# Sheet4.net
KiCad netlist of a schematic drawn in Altium Designer
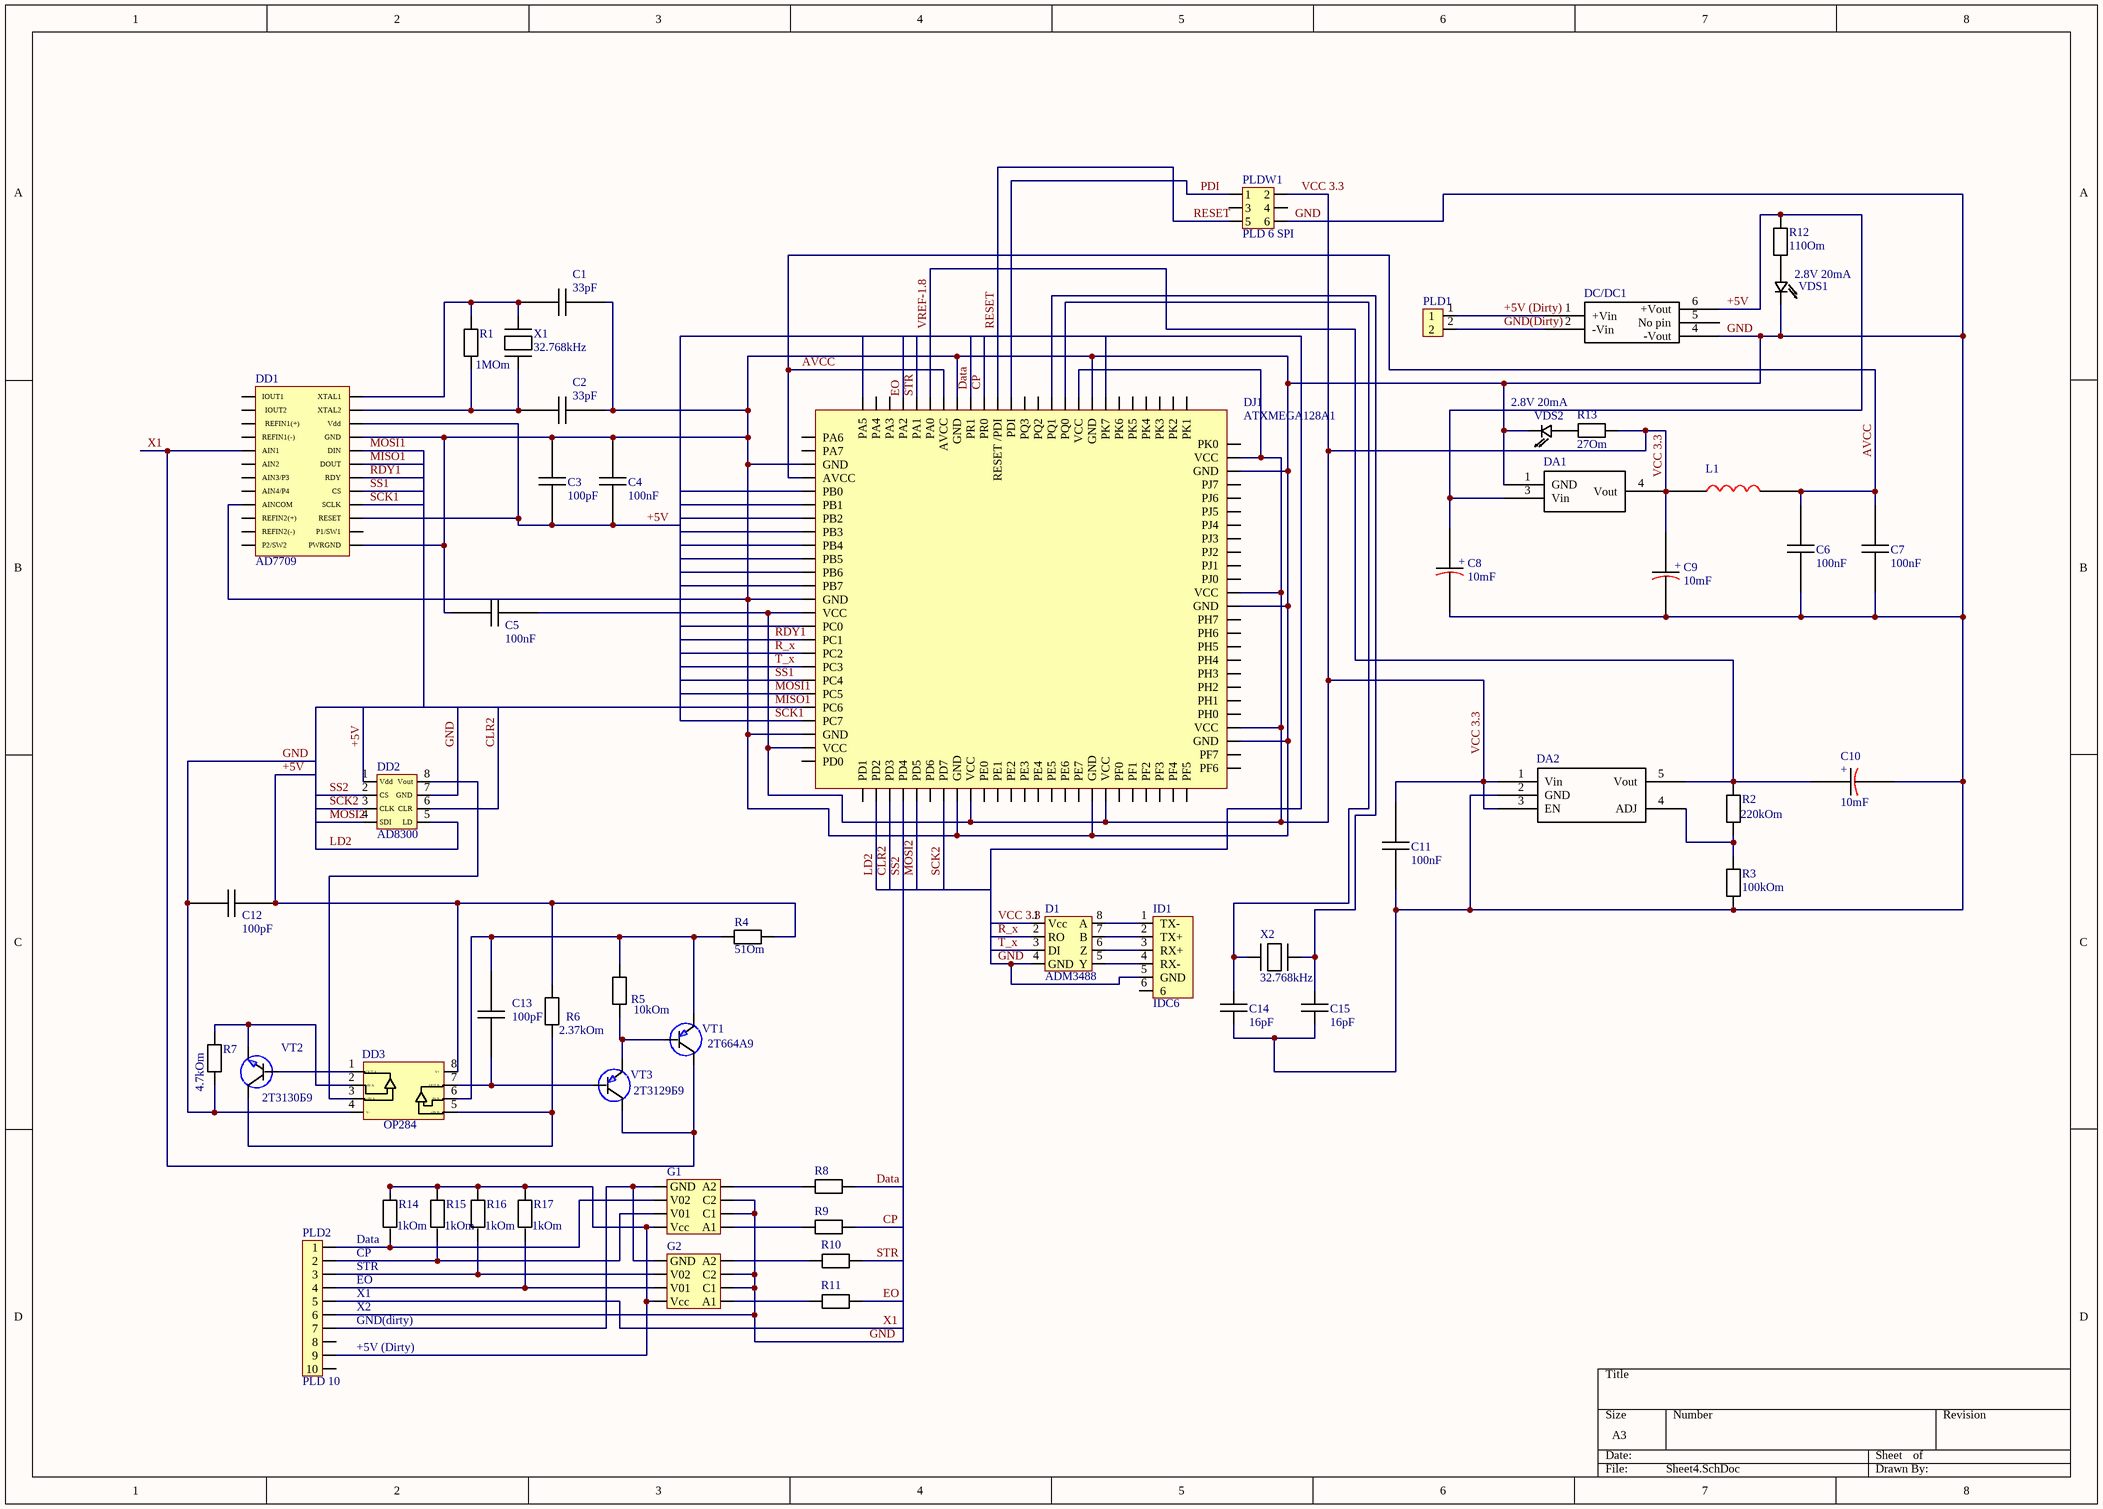
[diagram p0: Sheet4.SchDoc]

(export (version "E")
  (design (tool "Eeschema 10.0.6"))
  (components
    (comp (ref "C1") (value "33pF") (footprint "Cap 1206") (libsource (lib "Schlib1") (part "Cap 33pF")))
    (comp (ref "C2") (value "33pF") (footprint "Cap 1206") (libsource (lib "Schlib1") (part "Cap 33pF")))
    (comp (ref "C3") (value "100pF") (footprint "Cap 0805") (libsource (lib "Schlib1") (part "Cap 100 pF")))
    (comp (ref "C4") (value "100nF") (footprint "Cap 0805") (libsource (lib "Schlib1") (part "cap 100nF")))
    (comp (ref "C5") (value "100nF") (footprint "Cap 0805") (libsource (lib "Schlib1") (part "cap 100nF")))
    (comp (ref "C6") (value "100nF") (footprint "Cap 0805") (libsource (lib "Schlib1") (part "cap 100nF")))
    (comp (ref "C7") (value "100nF") (footprint "Cap 0805") (libsource (lib "Schlib1") (part "cap 100nF")))
    (comp (ref "C8")
      (value "10mF")
      (footprint "Cap 10mF electrolit")
      (libsource (lib "Schlib1") (part "Cap 10mF electrolit"))
    )
    (comp (ref "C9")
      (value "10mF")
      (footprint "Cap 10mF electrolit")
      (libsource (lib "Schlib1") (part "Cap 10mF electrolit"))
    )
    (comp (ref "C10")
      (value "10mF")
      (footprint "Cap 10mF electrolit")
      (libsource (lib "Schlib1") (part "Cap 10mF electrolit"))
    )
    (comp (ref "C11") (value "100nF") (footprint "Cap 0805") (libsource (lib "Schlib1") (part "cap 100nF")))
    (comp (ref "C12") (value "100pF") (footprint "Cap 0805") (libsource (lib "Schlib1") (part "Cap 100pF")))
    (comp (ref "C13") (value "100pF") (footprint "Cap 0805") (libsource (lib "Schlib1") (part "Cap 100pF")))
    (comp (ref "C14") (value "16pF") (footprint "Cap 0805") (libsource (lib "Schlib1") (part "Cap 22pF")))
    (comp (ref "C15") (value "16pF") (footprint "Cap 0805") (libsource (lib "Schlib1") (part "Cap 22pF")))
    (comp (ref "D1") (value "ADM3488") (footprint "ADM3488") (libsource (lib "Schlib1") (part "ADM3488")))
    (comp (ref "DA1") (value "~") (footprint "MC33269") (libsource (lib "Schlib1") (part "MC33269")))
    (comp (ref "DA2") (value "~") (footprint "MIC5205-ADJ") (libsource (lib "Schlib1") (part "MIC5205-ADJ")))
    (comp (ref "DC/DC1")
      (value "~")
      (footprint "TRACO POWER")
      (libsource (lib "Schlib1") (part "TRACO POWER(5V)"))
    )
    (comp (ref "DD1")
      (value "AD7709")
      (footprint "AD7709 TSSOP24")
      (libsource (lib "Schlib1") (part "AD7709"))
    )
    (comp (ref "DD2") (value "AD8300") (footprint "SOIC8") (libsource (lib "Schlib1") (part "AD8300")))
    (comp (ref "DD3") (value "OP284") (footprint "SOIC8") (libsource (lib "Schlib1") (part "OP284")))
    (comp (ref "DJ1")
      (value "ATXMEGA128A1")
      (footprint "ATXMEGA128A1")
      (libsource (lib "Schlib1") (part "ATXMEGA128A1"))
    )
    (comp (ref "G1")
      (value "~")
      (footprint "HCPL-0600/01/11/30/31/61 (HCPL-0631-000E)")
      (libsource (lib "altium-import") (part "root_2__Schlib1.SchLib"))
    )
    (comp (ref "G2")
      (value "~")
      (footprint "HCPL-0600/01/11/30/31/61 (HCPL-0631-000E)")
      (libsource (lib "altium-import") (part "root_2__Schlib1.SchLib"))
    )
    (comp (ref "ID1") (value "IDC6") (footprint "IDC 6") (libsource (lib "Schlib1") (part "IDC6")))
    (comp (ref "L1") (value "~") (footprint "Ind 10 mHe") (libsource (lib "Schlib1") (part "Ind 10 mHe")))
    (comp (ref "PLD1") (value "~") (footprint "PLS 2") (libsource (lib "Schlib1") (part "PLS 2")))
    (comp (ref "PLD2") (value "PLD 10") (footprint "PLD 10") (libsource (lib "Schlib1") (part "PLD 10")))
    (comp (ref "PLDW1")
      (value "PLD 6 SPI")
      (footprint "PLD 6 SPI")
      (libsource (lib "Schlib1") (part "PLD 6 SPI"))
    )
    (comp (ref "R1") (value "1MOm") (footprint "Res 1206") (libsource (lib "Schlib1") (part "RES 1MOm")))
    (comp (ref "R2") (value "220kOm") (footprint "Res 0805") (libsource (lib "Schlib1") (part "Res 100kOm")))
    (comp (ref "R3") (value "100kOm") (footprint "Res 0805") (libsource (lib "Schlib1") (part "Res 100kOm")))
    (comp (ref "R4") (value "51Om") (footprint "Res 1206") (libsource (lib "Schlib1") (part "RES 51Om")))
    (comp (ref "R5")
      (value "10kOm")
      (footprint "Res 1206")
      (libsource (lib "Schlib1") (part "RES 10kOm SMD1206"))
    )
    (comp (ref "R6")
      (value "2.37kOm")
      (footprint "Res 1206")
      (libsource (lib "Schlib1") (part "RES 2.37kOm"))
    )
    (comp (ref "R7") (value "4.7kOm") (footprint "Res 0805") (libsource (lib "Schlib1") (part "RES 4.6kOm")))
    (comp (ref "R8") (value "~") (footprint "Res 0805") (libsource (lib "Schlib1") (part "Res 100 Om")))
    (comp (ref "R9") (value "~") (footprint "Res 0805") (libsource (lib "Schlib1") (part "Res 100 Om")))
    (comp (ref "R10") (value "~") (footprint "Res 0805") (libsource (lib "Schlib1") (part "Res 100 Om")))
    (comp (ref "R11") (value "~") (footprint "Res 0805") (libsource (lib "Schlib1") (part "Res 100 Om")))
    (comp (ref "R12") (value "110Om") (footprint "Res 0805") (libsource (lib "Schlib1") (part "Res 110Om")))
    (comp (ref "R13") (value "27Om") (footprint "Res 0805") (libsource (lib "Schlib1") (part "Res 25Om")))
    (comp (ref "R14") (value "1kOm") (footprint "Cap 0603") (libsource (lib "Schlib1") (part "Res 1kOm")))
    (comp (ref "R15") (value "1kOm") (footprint "Cap 0603") (libsource (lib "Schlib1") (part "Res 1kOm")))
    (comp (ref "R16") (value "1kOm") (footprint "Cap 0603") (libsource (lib "Schlib1") (part "Res 1kOm")))
    (comp (ref "R17") (value "1kOm") (footprint "Cap 0603") (libsource (lib "Schlib1") (part "Res 1kOm")))
    (comp (ref "VDS1")
      (value "2.8V 20mA")
      (footprint "Под диод (5ммх2мм)")
      (libsource (lib "Schlib1") (part "Светодиод"))
    )
    (comp (ref "VDS2")
      (value "2.8V 20mA")
      (footprint "Под диод (5ммх2мм)")
      (libsource (lib "Schlib1") (part "Светодиод"))
    )
    (comp (ref "VT1") (value "2Т664А9") (footprint "2Т3129Б9") (libsource (lib "Schlib1") (part "2Т664А9")))
    (comp (ref "VT2") (value "2Т3130Б9") (footprint "2Т3129Б9") (libsource (lib "Schlib1") (part "2Т3130Б9")))
    (comp (ref "VT3") (value "2Т3129Б9") (footprint "2Т3129Б9") (libsource (lib "Schlib1") (part "2Т3129Б9")))
    (comp (ref "X1") (value "32.768kHz") (footprint "kvarz") (libsource (lib "Schlib1") (part "32.768kHz")))
    (comp (ref "X2") (value "32.768kHz") (footprint "kvarz") (libsource (lib "Schlib1") (part "32.768kHz")))
  )
  (nets
    (net (code "1") (name "/+5V") (class "Default")
      (node (ref "C12") (pin "2") (pinfunction "2_2") (pintype "passive"))
      (node (ref "C3") (pin "1") (pinfunction "1_1") (pintype "passive"))
      (node (ref "C4") (pin "1") (pinfunction "1_1") (pintype "passive"))
      (node (ref "C8") (pin "1") (pinfunction "1_1") (pintype "passive"))
      (node (ref "DA1") (pin "3") (pinfunction "Vin_3") (pintype "passive"))
      (node (ref "DC/DC1") (pin "6") (pinfunction "+Vout_6") (pintype "passive"))
      (node (ref "DD1") (pin "15") (pinfunction "RESET_15") (pintype "passive"))
      (node (ref "DD1") (pin "22") (pinfunction "Vdd_22") (pintype "passive"))
      (node (ref "DD2") (pin "1") (pinfunction "Vdd_1") (pintype "passive"))
      (node (ref "DD3") (pin "8") (pinfunction "V+_8") (pintype "passive"))
      (node (ref "R12") (pin "2") (pinfunction "2_2") (pintype "passive"))
      (node (ref "R4") (pin "2") (pinfunction "2_2") (pintype "passive"))
      (node (ref "R6") (pin "2") (pinfunction "2_2") (pintype "passive"))
    )
    (net (code "2") (name "/+5V (Dirty)") (class "Default")
      (node (ref "DC/DC1") (pin "1") (pinfunction "+Vin_1") (pintype "passive"))
      (node (ref "PLD1") (pin "1") (pinfunction "1_1") (pintype "passive"))
    )
    (net (code "3") (name "/AVCC") (class "Default")
      (node (ref "C6") (pin "2") (pinfunction "2_2") (pintype "passive"))
      (node (ref "C7") (pin "2") (pinfunction "2_2") (pintype "passive"))
      (node (ref "DJ1") (pin "H1") (pinfunction "AVCC_H1") (pintype "passive"))
      (node (ref "DJ1") (pin "K4") (pinfunction "AVCC_K4") (pintype "passive"))
      (node (ref "L1") (pin "2") (pinfunction "2_2") (pintype "passive"))
    )
    (net (code "4") (name "/CLR2") (class "Default")
      (node (ref "DD2") (pin "6") (pinfunction "CLR_6") (pintype "passive"))
      (node (ref "DJ1") (pin "H10") (pinfunction "PD3_H10") (pintype "passive"))
    )
    (net (code "5") (name "/CP") (class "Default")
      (node (ref "DJ1") (pin "F2") (pinfunction "PR0_F2") (pintype "passive"))
      (node (ref "R9") (pin "2") (pinfunction "2_2") (pintype "passive"))
    )
    (net (code "6") (name "/Data") (class "Default")
      (node (ref "DJ1") (pin "F1") (pinfunction "PR1_F1") (pintype "passive"))
      (node (ref "R8") (pin "2") (pinfunction "2_2") (pintype "passive"))
    )
    (net (code "7") (name "/EO") (class "Default")
      (node (ref "DJ1") (pin "H2") (pinfunction "PA2_H2") (pintype "passive"))
      (node (ref "R11") (pin "2") (pinfunction "2_2") (pintype "passive"))
    )
    (net (code "8") (name "/GND") (class "Default")
      (node (ref "C1") (pin "2") (pinfunction "2_2") (pintype "passive"))
      (node (ref "C10") (pin "2") (pinfunction "2_2") (pintype "passive"))
      (node (ref "C11") (pin "1") (pinfunction "1_1") (pintype "passive"))
      (node (ref "C12") (pin "1") (pinfunction "1_1") (pintype "passive"))
      (node (ref "C14") (pin "1") (pinfunction "1_1") (pintype "passive"))
      (node (ref "C15") (pin "1") (pinfunction "1_1") (pintype "passive"))
      (node (ref "C2") (pin "2") (pinfunction "2_2") (pintype "passive"))
      (node (ref "C3") (pin "2") (pinfunction "2_2") (pintype "passive"))
      (node (ref "C4") (pin "2") (pinfunction "2_2") (pintype "passive"))
      (node (ref "C5") (pin "1") (pinfunction "1_1") (pintype "passive"))
      (node (ref "C6") (pin "1") (pinfunction "1_1") (pintype "passive"))
      (node (ref "C7") (pin "1") (pinfunction "1_1") (pintype "passive"))
      (node (ref "C8") (pin "2") (pinfunction "2_2") (pintype "passive"))
      (node (ref "C9") (pin "2") (pinfunction "2_2") (pintype "passive"))
      (node (ref "D1") (pin "4") (pinfunction "GND_4") (pintype "passive"))
      (node (ref "DA1") (pin "1") (pinfunction "GND_1") (pintype "passive"))
      (node (ref "DA2") (pin "2") (pinfunction "GND_2") (pintype "passive"))
      (node (ref "DC/DC1") (pin "4") (pinfunction "-Vout_4") (pintype "passive"))
      (node (ref "DD1") (pin "13") (pinfunction "PWRGND_13") (pintype "passive"))
      (node (ref "DD1") (pin "21") (pinfunction "GND_21") (pintype "passive"))
      (node (ref "DD1") (pin "9") (pinfunction "AINCOM_9") (pintype "passive"))
      (node (ref "DD2") (pin "7") (pinfunction "GND_7") (pintype "passive"))
      (node (ref "DD3") (pin "4") (pinfunction "V-_4") (pintype "passive"))
      (node (ref "DJ1") (pin "A3") (pinfunction "GND_A3") (pintype "passive"))
      (node (ref "DJ1") (pin "A6") (pinfunction "GND_A6") (pintype "passive"))
      (node (ref "DJ1") (pin "A8") (pinfunction "GND_A8") (pintype "passive"))
      (node (ref "DJ1") (pin "D1") (pinfunction "GND_D1") (pintype "passive"))
      (node (ref "DJ1") (pin "D10") (pinfunction "GND_D10") (pintype "passive"))
      (node (ref "DJ1") (pin "G1") (pinfunction "GND_G1") (pintype "passive"))
      (node (ref "DJ1") (pin "G10") (pinfunction "GND_G10") (pintype "passive"))
      (node (ref "DJ1") (pin "K3") (pinfunction "GND_K3") (pintype "passive"))
      (node (ref "DJ1") (pin "K7") (pinfunction "GND_K7") (pintype "passive"))
      (node (ref "DJ1") (pin "K9") (pinfunction "GND_K9") (pintype "passive"))
      (node (ref "G1") (pin "2") (pinfunction "C1_2") (pintype "passive"))
      (node (ref "G1") (pin "3") (pinfunction "C2_3") (pintype "passive"))
      (node (ref "G2") (pin "2") (pinfunction "C1_2") (pintype "passive"))
      (node (ref "G2") (pin "3") (pinfunction "C2_3") (pintype "passive"))
      (node (ref "ID1") (pin "5") (pinfunction "GND_5") (pintype "passive"))
      (node (ref "PLD2") (pin "6") (pinfunction "6_6") (pintype "passive"))
      (node (ref "PLDW1") (pin "6") (pinfunction "6_6") (pintype "passive"))
      (node (ref "R3") (pin "1") (pinfunction "1_1") (pintype "passive"))
      (node (ref "R7") (pin "1") (pinfunction "1_1") (pintype "passive"))
      (node (ref "VDS1") (pin "2") (pinfunction "2_2") (pintype "passive"))
      (node (ref "VDS2") (pin "2") (pinfunction "2_2") (pintype "passive"))
    )
    (net (code "9") (name "/GND(Dirty)") (class "Default")
      (node (ref "DC/DC1") (pin "2") (pinfunction "-Vin_2") (pintype "passive"))
      (node (ref "PLD1") (pin "2") (pinfunction "2_2") (pintype "passive"))
    )
    (net (code "10") (name "/LD2") (class "Default")
      (node (ref "DD2") (pin "5") (pinfunction "LD_5") (pintype "passive"))
      (node (ref "DJ1") (pin "J9") (pinfunction "PD2_J9") (pintype "passive"))
    )
    (net (code "11") (name "/MISO1") (class "Default")
      (node (ref "DD1") (pin "19") (pinfunction "DOUT_19") (pintype "passive"))
      (node (ref "DJ1") (pin "G7") (pinfunction "PC6_G7") (pintype "passive"))
    )
    (net (code "12") (name "/MOSI1") (class "Default")
      (node (ref "DD1") (pin "20") (pinfunction "DIN_20") (pintype "passive"))
      (node (ref "DJ1") (pin "H7") (pinfunction "PC5_H7") (pintype "passive"))
    )
    (net (code "13") (name "/MOSI2") (class "Default")
      (node (ref "DD2") (pin "4") (pinfunction "SDI_4") (pintype "passive"))
      (node (ref "DJ1") (pin "H8") (pinfunction "PD5_H8") (pintype "passive"))
    )
    (net (code "14") (name "/PDI") (class "Default")
      (node (ref "DJ1") (pin "F4") (pinfunction "PDI_F4") (pintype "passive"))
      (node (ref "PLDW1") (pin "1") (pinfunction "1_1") (pintype "passive"))
    )
    (net (code "15") (name "/RDY1") (class "Default")
      (node (ref "DD1") (pin "18") (pinfunction "RDY_18") (pintype "passive"))
      (node (ref "DJ1") (pin "G6") (pinfunction "PC1_G6") (pintype "passive"))
    )
    (net (code "16") (name "/RESET") (class "Default")
      (node (ref "DJ1") (pin "F3") (pinfunction "RESET_/PDI_F3") (pintype "passive"))
      (node (ref "PLDW1") (pin "5") (pinfunction "5_5") (pintype "passive"))
    )
    (net (code "17") (name "/R_x") (class "Default")
      (node (ref "D1") (pin "2") (pinfunction "RO_2") (pintype "passive"))
      (node (ref "DJ1") (pin "F6") (pinfunction "PC2_F6") (pintype "passive"))
    )
    (net (code "18") (name "/SCK1") (class "Default")
      (node (ref "DD1") (pin "16") (pinfunction "SCLK_16") (pintype "passive"))
      (node (ref "DJ1") (pin "J8") (pinfunction "PC7_J8") (pintype "passive"))
    )
    (net (code "19") (name "/SCK2") (class "Default")
      (node (ref "DD2") (pin "3") (pinfunction "CLK_3") (pintype "passive"))
      (node (ref "DJ1") (pin "G8") (pinfunction "PD7_G8") (pintype "passive"))
    )
    (net (code "20") (name "/SS1") (class "Default")
      (node (ref "DD1") (pin "17") (pinfunction "CS_17") (pintype "passive"))
      (node (ref "DJ1") (pin "J7") (pinfunction "PC4_J7") (pintype "passive"))
    )
    (net (code "21") (name "/SS2") (class "Default")
      (node (ref "DD2") (pin "2") (pinfunction "CS_2") (pintype "passive"))
      (node (ref "DJ1") (pin "H9") (pinfunction "PD4_H9") (pintype "passive"))
    )
    (net (code "22") (name "/STR") (class "Default")
      (node (ref "DJ1") (pin "G2") (pinfunction "PA1_G2") (pintype "passive"))
      (node (ref "R10") (pin "2") (pinfunction "2_2") (pintype "passive"))
    )
    (net (code "23") (name "/T_x") (class "Default")
      (node (ref "D1") (pin "3") (pinfunction "DI_3") (pintype "passive"))
      (node (ref "DJ1") (pin "J6") (pinfunction "PC3_J6") (pintype "passive"))
    )
    (net (code "24") (name "/VCC 3.3") (class "Default")
      (node (ref "C11") (pin "2") (pinfunction "2_2") (pintype "passive"))
      (node (ref "C5") (pin "2") (pinfunction "2_2") (pintype "passive"))
      (node (ref "C9") (pin "1") (pinfunction "1_1") (pintype "passive"))
      (node (ref "D1") (pin "1") (pinfunction "Vcc_1") (pintype "passive"))
      (node (ref "DA1") (pin "4") (pinfunction "Vout_4") (pintype "passive"))
      (node (ref "DA2") (pin "1") (pinfunction "Vin_1") (pintype "passive"))
      (node (ref "DA2") (pin "3") (pinfunction "EN_3") (pintype "passive"))
      (node (ref "DJ1") (pin "A2") (pinfunction "VCC_A2") (pintype "passive"))
      (node (ref "DJ1") (pin "A5") (pinfunction "VCC_A5") (pintype "passive"))
      (node (ref "DJ1") (pin "A9") (pinfunction "VCC_A9") (pintype "passive"))
      (node (ref "DJ1") (pin "C1") (pinfunction "VCC_C1") (pintype "passive"))
      (node (ref "DJ1") (pin "C10") (pinfunction "VCC_C10") (pintype "passive"))
      (node (ref "DJ1") (pin "F10") (pinfunction "VCC_F10") (pintype "passive"))
      (node (ref "DJ1") (pin "K6") (pinfunction "VCC_K6") (pintype "passive"))
      (node (ref "DJ1") (pin "K8") (pinfunction "VCC_K8") (pintype "passive"))
      (node (ref "L1") (pin "1") (pinfunction "1_1") (pintype "passive"))
      (node (ref "PLDW1") (pin "2") (pinfunction "2_2") (pintype "passive"))
      (node (ref "R13") (pin "1") (pinfunction "1_1") (pintype "passive"))
    )
    (net (code "25") (name "/VREF-1.8") (class "Default")
      (node (ref "C10") (pin "1") (pinfunction "1_1") (pintype "passive"))
      (node (ref "DA2") (pin "5") (pinfunction "Vout_5") (pintype "passive"))
      (node (ref "DJ1") (pin "J1") (pinfunction "PA0_J1") (pintype "passive"))
      (node (ref "R2") (pin "2") (pinfunction "2_2") (pintype "passive"))
    )
    (net (code "26") (name "/X1") (class "Default")
      (node (ref "DD1") (pin "5") (pinfunction "AIN1_5") (pintype "passive"))
      (node (ref "PLD2") (pin "5") (pinfunction "5_5") (pintype "passive"))
      (node (ref "VT1") (pin "1") (pinfunction "1_1") (pintype "passive"))
      (node (ref "VT3") (pin "2") (pinfunction "2_2") (pintype "passive"))
    )
    (net (code "27") (name "Net-(D1-A)") (class "Default")
      (node (ref "D1") (pin "8") (pinfunction "A_8") (pintype "passive"))
      (node (ref "ID1") (pin "1") (pinfunction "TX-_1") (pintype "passive"))
    )
    (net (code "28") (name "Net-(D1-B)") (class "Default")
      (node (ref "D1") (pin "7") (pinfunction "B_7") (pintype "passive"))
      (node (ref "ID1") (pin "2") (pinfunction "TX+_2") (pintype "passive"))
    )
    (net (code "29") (name "Net-(D1-Y)") (class "Default")
      (node (ref "D1") (pin "5") (pinfunction "Y_5") (pintype "passive"))
      (node (ref "ID1") (pin "4") (pinfunction "RX-_4") (pintype "passive"))
    )
    (net (code "30") (name "Net-(D1-Z)") (class "Default")
      (node (ref "D1") (pin "6") (pinfunction "Z_6") (pintype "passive"))
      (node (ref "ID1") (pin "3") (pinfunction "RX+_3") (pintype "passive"))
    )
    (net (code "31") (name "Net-(DA2-ADJ)") (class "Default")
      (node (ref "DA2") (pin "4") (pinfunction "ADJ_4") (pintype "passive"))
      (node (ref "R2") (pin "1") (pinfunction "1_1") (pintype "passive"))
      (node (ref "R3") (pin "2") (pinfunction "2_2") (pintype "passive"))
    )
    (net (code "32") (name "Net-(DD1-XTAL1)") (class "Default")
      (node (ref "C1") (pin "1") (pinfunction "1_1") (pintype "passive"))
      (node (ref "DD1") (pin "24") (pinfunction "XTAL1_24") (pintype "passive"))
      (node (ref "R1") (pin "2") (pinfunction "2_2") (pintype "passive"))
      (node (ref "X1") (pin "2") (pinfunction "2_2") (pintype "passive"))
    )
    (net (code "33") (name "Net-(DD1-XTAL2)") (class "Default")
      (node (ref "C2") (pin "1") (pinfunction "1_1") (pintype "passive"))
      (node (ref "DD1") (pin "23") (pinfunction "XTAL2_23") (pintype "passive"))
      (node (ref "R1") (pin "1") (pinfunction "1_1") (pintype "passive"))
      (node (ref "X1") (pin "1") (pinfunction "1_1") (pintype "passive"))
    )
    (net (code "34") (name "Net-(DD2-Vout)") (class "Default")
      (node (ref "DD2") (pin "8") (pinfunction "Vout_8") (pintype "passive"))
      (node (ref "DD3") (pin "3") (pinfunction "+IN_A_3") (pintype "passive"))
    )
    (net (code "35") (name "Net-(DD3-+IN_B)") (class "Default")
      (node (ref "DD3") (pin "5") (pinfunction "+IN_B_5") (pintype "passive"))
      (node (ref "R6") (pin "1") (pinfunction "1_1") (pintype "passive"))
      (node (ref "VT2") (pin "2") (pinfunction "2_2") (pintype "passive"))
    )
    (net (code "36") (name "Net-(DD3--IN_A)") (class "Default")
      (node (ref "DD3") (pin "2") (pinfunction "-IN_A_2") (pintype "passive"))
      (node (ref "R7") (pin "2") (pinfunction "2_2") (pintype "passive"))
      (node (ref "VT2") (pin "3") (pinfunction "3_3") (pintype "passive"))
    )
    (net (code "37") (name "Net-(DD3--IN_B)") (class "Default")
      (node (ref "C13") (pin "1") (pinfunction "1_1") (pintype "passive"))
      (node (ref "DD3") (pin "6") (pinfunction "-IN_B_6") (pintype "passive"))
      (node (ref "R4") (pin "1") (pinfunction "1_1") (pintype "passive"))
      (node (ref "R5") (pin "2") (pinfunction "2_2") (pintype "passive"))
      (node (ref "VT1") (pin "3") (pinfunction "3_3") (pintype "passive"))
    )
    (net (code "38") (name "Net-(DD3-OUT_A)") (class "Default")
      (node (ref "DD3") (pin "1") (pinfunction "OUT_A_1") (pintype "passive"))
      (node (ref "VT2") (pin "1") (pinfunction "1_1") (pintype "passive"))
    )
    (net (code "39") (name "Net-(DD3-OUT_B)") (class "Default")
      (node (ref "C13") (pin "2") (pinfunction "2_2") (pintype "passive"))
      (node (ref "DD3") (pin "7") (pinfunction "OUT_B_7") (pintype "passive"))
      (node (ref "VT3") (pin "1") (pinfunction "1_1") (pintype "passive"))
    )
    (net (code "40") (name "Net-(DJ1-PQ0)") (class "Default")
      (node (ref "C14") (pin "2") (pinfunction "2_2") (pintype "passive"))
      (node (ref "DJ1") (pin "E1") (pinfunction "PQ0_E1") (pintype "passive"))
      (node (ref "X2") (pin "1") (pinfunction "1_1") (pintype "passive"))
    )
    (net (code "41") (name "Net-(DJ1-PQ1)") (class "Default")
      (node (ref "C15") (pin "2") (pinfunction "2_2") (pintype "passive"))
      (node (ref "DJ1") (pin "E2") (pinfunction "PQ1_E2") (pintype "passive"))
      (node (ref "X2") (pin "2") (pinfunction "2_2") (pintype "passive"))
    )
    (net (code "42") (name "Net-(G1-A1)") (class "Default")
      (node (ref "G1") (pin "1") (pinfunction "A1_1") (pintype "passive"))
      (node (ref "R9") (pin "1") (pinfunction "1_1") (pintype "passive"))
    )
    (net (code "43") (name "Net-(G1-A2)") (class "Default")
      (node (ref "G1") (pin "4") (pinfunction "A2_4") (pintype "passive"))
      (node (ref "R8") (pin "1") (pinfunction "1_1") (pintype "passive"))
    )
    (net (code "44") (name "Net-(G1-GND)") (class "Default")
      (node (ref "G1") (pin "5") (pinfunction "GND_5") (pintype "passive"))
      (node (ref "G2") (pin "5") (pinfunction "GND_5") (pintype "passive"))
      (node (ref "PLD2") (pin "7") (pinfunction "7_7") (pintype "passive"))
    )
    (net (code "45") (name "Net-(G1-V01)") (class "Default")
      (node (ref "G1") (pin "7") (pinfunction "V01_7") (pintype "passive"))
      (node (ref "PLD2") (pin "2") (pinfunction "2_2") (pintype "passive"))
      (node (ref "R15") (pin "1") (pinfunction "1_1") (pintype "passive"))
    )
    (net (code "46") (name "Net-(G1-V02)") (class "Default")
      (node (ref "G1") (pin "6") (pinfunction "V02_6") (pintype "passive"))
      (node (ref "PLD2") (pin "1") (pinfunction "1_1") (pintype "passive"))
      (node (ref "R14") (pin "1") (pinfunction "1_1") (pintype "passive"))
    )
    (net (code "47") (name "Net-(G1-Vcc)") (class "Default")
      (node (ref "G1") (pin "8") (pinfunction "Vcc_8") (pintype "passive"))
      (node (ref "G2") (pin "8") (pinfunction "Vcc_8") (pintype "passive"))
      (node (ref "PLD2") (pin "9") (pinfunction "9_9") (pintype "passive"))
      (node (ref "R14") (pin "2") (pinfunction "2_2") (pintype "passive"))
      (node (ref "R15") (pin "2") (pinfunction "2_2") (pintype "passive"))
      (node (ref "R16") (pin "2") (pinfunction "2_2") (pintype "passive"))
      (node (ref "R17") (pin "2") (pinfunction "2_2") (pintype "passive"))
    )
    (net (code "48") (name "Net-(G2-A1)") (class "Default")
      (node (ref "G2") (pin "1") (pinfunction "A1_1") (pintype "passive"))
      (node (ref "R11") (pin "1") (pinfunction "1_1") (pintype "passive"))
    )
    (net (code "49") (name "Net-(G2-A2)") (class "Default")
      (node (ref "G2") (pin "4") (pinfunction "A2_4") (pintype "passive"))
      (node (ref "R10") (pin "1") (pinfunction "1_1") (pintype "passive"))
    )
    (net (code "50") (name "Net-(G2-V01)") (class "Default")
      (node (ref "G2") (pin "7") (pinfunction "V01_7") (pintype "passive"))
      (node (ref "PLD2") (pin "4") (pinfunction "4_4") (pintype "passive"))
      (node (ref "R17") (pin "1") (pinfunction "1_1") (pintype "passive"))
    )
    (net (code "51") (name "Net-(G2-V02)") (class "Default")
      (node (ref "G2") (pin "6") (pinfunction "V02_6") (pintype "passive"))
      (node (ref "PLD2") (pin "3") (pinfunction "3_3") (pintype "passive"))
      (node (ref "R16") (pin "1") (pinfunction "1_1") (pintype "passive"))
    )
    (net (code "52") (name "Net-(R5-Pad1)") (class "Default")
      (node (ref "R5") (pin "1") (pinfunction "1_1") (pintype "passive"))
      (node (ref "VT1") (pin "2") (pinfunction "2_2") (pintype "passive"))
      (node (ref "VT3") (pin "3") (pinfunction "3_3") (pintype "passive"))
    )
    (net (code "53") (name "Net-(R12-Pad1)") (class "Default")
      (node (ref "R12") (pin "1") (pinfunction "1_1") (pintype "passive"))
      (node (ref "VDS1") (pin "1") (pinfunction "1_1") (pintype "passive"))
    )
    (net (code "54") (name "Net-(R13-Pad2)") (class "Default")
      (node (ref "R13") (pin "2") (pinfunction "2_2") (pintype "passive"))
      (node (ref "VDS2") (pin "1") (pinfunction "1_1") (pintype "passive"))
    )
    (net (code "55") (name "unconnected-(DC/DC1-No_pin-Pad5)") (class "Default")
      (node (ref "DC/DC1") (pin "5") (pinfunction "No_pin_5") (pintype "passive"))
    )
    (net (code "56") (name "unconnected-(DD1-AIN2-Pad6)") (class "Default")
      (node (ref "DD1") (pin "6") (pinfunction "AIN2_6") (pintype "passive"))
    )
    (net (code "57") (name "unconnected-(DD1-AIN3{slash}P3-Pad7)") (class "Default")
      (node (ref "DD1") (pin "7") (pinfunction "AIN3/P3_7") (pintype "passive"))
    )
    (net (code "58") (name "unconnected-(DD1-AIN4{slash}P4-Pad8)") (class "Default")
      (node (ref "DD1") (pin "8") (pinfunction "AIN4/P4_8") (pintype "passive"))
    )
    (net (code "59") (name "unconnected-(DD1-IOUT1-Pad1)") (class "Default")
      (node (ref "DD1") (pin "1") (pinfunction "IOUT1_1") (pintype "passive"))
    )
    (net (code "60") (name "unconnected-(DD1-IOUT2-Pad2)") (class "Default")
      (node (ref "DD1") (pin "2") (pinfunction "IOUT2_2") (pintype "passive"))
    )
    (net (code "61") (name "unconnected-(DD1-P1{slash}SW1-Pad14)") (class "Default")
      (node (ref "DD1") (pin "14") (pinfunction "P1/SW1_14") (pintype "passive"))
    )
    (net (code "62") (name "unconnected-(DD1-P2{slash}SW2-Pad12)") (class "Default")
      (node (ref "DD1") (pin "12") (pinfunction "P2/SW2_12") (pintype "passive"))
    )
    (net (code "63") (name "unconnected-(DD1-REFIN1(+)-Pad3)") (class "Default")
      (node (ref "DD1") (pin "3") (pinfunction "REFIN1(+)_3") (pintype "passive"))
    )
    (net (code "64") (name "unconnected-(DD1-REFIN1(-)-Pad4)") (class "Default")
      (node (ref "DD1") (pin "4") (pinfunction "REFIN1(-)_4") (pintype "passive"))
    )
    (net (code "65") (name "unconnected-(DD1-REFIN2(+)-Pad10)") (class "Default")
      (node (ref "DD1") (pin "10") (pinfunction "REFIN2(+)_10") (pintype "passive"))
    )
    (net (code "66") (name "unconnected-(DD1-REFIN2(-)-Pad11)") (class "Default")
      (node (ref "DD1") (pin "11") (pinfunction "REFIN2(-)_11") (pintype "passive"))
    )
    (net (code "67") (name "unconnected-(DJ1-PA3-PadJ2)") (class "Default")
      (node (ref "DJ1") (pin "J2") (pinfunction "PA3_J2") (pintype "passive"))
    )
    (net (code "68") (name "unconnected-(DJ1-PA4-PadG3)") (class "Default")
      (node (ref "DJ1") (pin "G3") (pinfunction "PA4_G3") (pintype "passive"))
    )
    (net (code "69") (name "unconnected-(DJ1-PA5-PadH3)") (class "Default")
      (node (ref "DJ1") (pin "H3") (pinfunction "PA5_H3") (pintype "passive"))
    )
    (net (code "70") (name "unconnected-(DJ1-PA6-PadK1)") (class "Default")
      (node (ref "DJ1") (pin "K1") (pinfunction "PA6_K1") (pintype "passive"))
    )
    (net (code "71") (name "unconnected-(DJ1-PA7-PadK2)") (class "Default")
      (node (ref "DJ1") (pin "K2") (pinfunction "PA7_K2") (pintype "passive"))
    )
    (net (code "72") (name "unconnected-(DJ1-PB0-PadJ3)") (class "Default")
      (node (ref "DJ1") (pin "J3") (pinfunction "PB0_J3") (pintype "passive"))
    )
    (net (code "73") (name "unconnected-(DJ1-PB1-PadJ4)") (class "Default")
      (node (ref "DJ1") (pin "J4") (pinfunction "PB1_J4") (pintype "passive"))
    )
    (net (code "74") (name "unconnected-(DJ1-PB2-PadH4)") (class "Default")
      (node (ref "DJ1") (pin "H4") (pinfunction "PB2_H4") (pintype "passive"))
    )
    (net (code "75") (name "unconnected-(DJ1-PB3-PadG4)") (class "Default")
      (node (ref "DJ1") (pin "G4") (pinfunction "PB3_G4") (pintype "passive"))
    )
    (net (code "76") (name "unconnected-(DJ1-PB4-PadG5)") (class "Default")
      (node (ref "DJ1") (pin "G5") (pinfunction "PB4_G5") (pintype "passive"))
    )
    (net (code "77") (name "unconnected-(DJ1-PB5-PadH5)") (class "Default")
      (node (ref "DJ1") (pin "H5") (pinfunction "PB5_H5") (pintype "passive"))
    )
    (net (code "78") (name "unconnected-(DJ1-PB6-PadJ5)") (class "Default")
      (node (ref "DJ1") (pin "J5") (pinfunction "PB6_J5") (pintype "passive"))
    )
    (net (code "79") (name "unconnected-(DJ1-PB7-PadK5)") (class "Default")
      (node (ref "DJ1") (pin "K5") (pinfunction "PB7_K5") (pintype "passive"))
    )
    (net (code "80") (name "unconnected-(DJ1-PC0-PadH6)") (class "Default")
      (node (ref "DJ1") (pin "H6") (pinfunction "PC0_H6") (pintype "passive"))
    )
    (net (code "81") (name "unconnected-(DJ1-PD0-PadK10)") (class "Default")
      (node (ref "DJ1") (pin "K10") (pinfunction "PD0_K10") (pintype "passive"))
    )
    (net (code "82") (name "unconnected-(DJ1-PD1-PadJ10)") (class "Default")
      (node (ref "DJ1") (pin "J10") (pinfunction "PD1_J10") (pintype "passive"))
    )
    (net (code "83") (name "unconnected-(DJ1-PD6-PadG9)") (class "Default")
      (node (ref "DJ1") (pin "G9") (pinfunction "PD6_G9") (pintype "passive"))
    )
    (net (code "84") (name "unconnected-(DJ1-PE0-PadF9)") (class "Default")
      (node (ref "DJ1") (pin "F9") (pinfunction "PE0_F9") (pintype "passive"))
    )
    (net (code "85") (name "unconnected-(DJ1-PE1-PadF8)") (class "Default")
      (node (ref "DJ1") (pin "F8") (pinfunction "PE1_F8") (pintype "passive"))
    )
    (net (code "86") (name "unconnected-(DJ1-PE2-PadF7)") (class "Default")
      (node (ref "DJ1") (pin "F7") (pinfunction "PE2_F7") (pintype "passive"))
    )
    (net (code "87") (name "unconnected-(DJ1-PE3-PadE10)") (class "Default")
      (node (ref "DJ1") (pin "E10") (pinfunction "PE3_E10") (pintype "passive"))
    )
    (net (code "88") (name "unconnected-(DJ1-PE4-PadE9)") (class "Default")
      (node (ref "DJ1") (pin "E9") (pinfunction "PE4_E9") (pintype "passive"))
    )
    (net (code "89") (name "unconnected-(DJ1-PE5-PadE8)") (class "Default")
      (node (ref "DJ1") (pin "E8") (pinfunction "PE5_E8") (pintype "passive"))
    )
    (net (code "90") (name "unconnected-(DJ1-PE6-PadE7)") (class "Default")
      (node (ref "DJ1") (pin "E7") (pinfunction "PE6_E7") (pintype "passive"))
    )
    (net (code "91") (name "unconnected-(DJ1-PE7-PadE6)") (class "Default")
      (node (ref "DJ1") (pin "E6") (pinfunction "PE7_E6") (pintype "passive"))
    )
    (net (code "92") (name "unconnected-(DJ1-PF0-PadD7)") (class "Default")
      (node (ref "DJ1") (pin "D7") (pinfunction "PF0_D7") (pintype "passive"))
    )
    (net (code "93") (name "unconnected-(DJ1-PF1-PadD8)") (class "Default")
      (node (ref "DJ1") (pin "D8") (pinfunction "PF1_D8") (pintype "passive"))
    )
    (net (code "94") (name "unconnected-(DJ1-PF2-PadC8)") (class "Default")
      (node (ref "DJ1") (pin "C8") (pinfunction "PF2_C8") (pintype "passive"))
    )
    (net (code "95") (name "unconnected-(DJ1-PF3-PadC9)") (class "Default")
      (node (ref "DJ1") (pin "C9") (pinfunction "PF3_C9") (pintype "passive"))
    )
    (net (code "96") (name "unconnected-(DJ1-PF4-PadD9)") (class "Default")
      (node (ref "DJ1") (pin "D9") (pinfunction "PF4_D9") (pintype "passive"))
    )
    (net (code "97") (name "unconnected-(DJ1-PF5-PadB10)") (class "Default")
      (node (ref "DJ1") (pin "B10") (pinfunction "PF5_B10") (pintype "passive"))
    )
    (net (code "98") (name "unconnected-(DJ1-PF6-PadB9)") (class "Default")
      (node (ref "DJ1") (pin "B9") (pinfunction "PF6_B9") (pintype "passive"))
    )
    (net (code "99") (name "unconnected-(DJ1-PF7-PadA10)") (class "Default")
      (node (ref "DJ1") (pin "A10") (pinfunction "PF7_A10") (pintype "passive"))
    )
    (net (code "100") (name "unconnected-(DJ1-PH0-PadB8)") (class "Default")
      (node (ref "DJ1") (pin "B8") (pinfunction "PH0_B8") (pintype "passive"))
    )
    (net (code "101") (name "unconnected-(DJ1-PH1-PadA7)") (class "Default")
      (node (ref "DJ1") (pin "A7") (pinfunction "PH1_A7") (pintype "passive"))
    )
    (net (code "102") (name "unconnected-(DJ1-PH2-PadB7)") (class "Default")
      (node (ref "DJ1") (pin "B7") (pinfunction "PH2_B7") (pintype "passive"))
    )
    (net (code "103") (name "unconnected-(DJ1-PH3-PadC7)") (class "Default")
      (node (ref "DJ1") (pin "C7") (pinfunction "PH3_C7") (pintype "passive"))
    )
    (net (code "104") (name "unconnected-(DJ1-PH4-PadB6)") (class "Default")
      (node (ref "DJ1") (pin "B6") (pinfunction "PH4_B6") (pintype "passive"))
    )
    (net (code "105") (name "unconnected-(DJ1-PH5-PadC6)") (class "Default")
      (node (ref "DJ1") (pin "C6") (pinfunction "PH5_C6") (pintype "passive"))
    )
    (net (code "106") (name "unconnected-(DJ1-PH6-PadD6)") (class "Default")
      (node (ref "DJ1") (pin "D6") (pinfunction "PH6_D6") (pintype "passive"))
    )
    (net (code "107") (name "unconnected-(DJ1-PH7-PadB5)") (class "Default")
      (node (ref "DJ1") (pin "B5") (pinfunction "PH7_B5") (pintype "passive"))
    )
    (net (code "108") (name "unconnected-(DJ1-PJ0-PadC5)") (class "Default")
      (node (ref "DJ1") (pin "C5") (pinfunction "PJ0_C5") (pintype "passive"))
    )
    (net (code "109") (name "unconnected-(DJ1-PJ1-PadD5)") (class "Default")
      (node (ref "DJ1") (pin "D5") (pinfunction "PJ1_D5") (pintype "passive"))
    )
    (net (code "110") (name "unconnected-(DJ1-PJ2-PadE5)") (class "Default")
      (node (ref "DJ1") (pin "E5") (pinfunction "PJ2_E5") (pintype "passive"))
    )
    (net (code "111") (name "unconnected-(DJ1-PJ3-PadA4)") (class "Default")
      (node (ref "DJ1") (pin "A4") (pinfunction "PJ3_A4") (pintype "passive"))
    )
    (net (code "112") (name "unconnected-(DJ1-PJ4-PadB4)") (class "Default")
      (node (ref "DJ1") (pin "B4") (pinfunction "PJ4_B4") (pintype "passive"))
    )
    (net (code "113") (name "unconnected-(DJ1-PJ5-PadC4)") (class "Default")
      (node (ref "DJ1") (pin "C4") (pinfunction "PJ5_C4") (pintype "passive"))
    )
    (net (code "114") (name "unconnected-(DJ1-PJ6-PadD4)") (class "Default")
      (node (ref "DJ1") (pin "D4") (pinfunction "PJ6_D4") (pintype "passive"))
    )
    (net (code "115") (name "unconnected-(DJ1-PJ7-PadE4)") (class "Default")
      (node (ref "DJ1") (pin "E4") (pinfunction "PJ7_E4") (pintype "passive"))
    )
    (net (code "116") (name "unconnected-(DJ1-PK0-PadA1)") (class "Default")
      (node (ref "DJ1") (pin "A1") (pinfunction "PK0_A1") (pintype "passive"))
    )
    (net (code "117") (name "unconnected-(DJ1-PK1-PadB3)") (class "Default")
      (node (ref "DJ1") (pin "B3") (pinfunction "PK1_B3") (pintype "passive"))
    )
    (net (code "118") (name "unconnected-(DJ1-PK2-PadB2)") (class "Default")
      (node (ref "DJ1") (pin "B2") (pinfunction "PK2_B2") (pintype "passive"))
    )
    (net (code "119") (name "unconnected-(DJ1-PK3-PadB1)") (class "Default")
      (node (ref "DJ1") (pin "B1") (pinfunction "PK3_B1") (pintype "passive"))
    )
    (net (code "120") (name "unconnected-(DJ1-PK4-PadC3)") (class "Default")
      (node (ref "DJ1") (pin "C3") (pinfunction "PK4_C3") (pintype "passive"))
    )
    (net (code "121") (name "unconnected-(DJ1-PK5-PadC2)") (class "Default")
      (node (ref "DJ1") (pin "C2") (pinfunction "PK5_C2") (pintype "passive"))
    )
    (net (code "122") (name "unconnected-(DJ1-PK6-PadD2)") (class "Default")
      (node (ref "DJ1") (pin "D2") (pinfunction "PK6_D2") (pintype "passive"))
    )
    (net (code "123") (name "unconnected-(DJ1-PK7-PadD3)") (class "Default")
      (node (ref "DJ1") (pin "D3") (pinfunction "PK7_D3") (pintype "passive"))
    )
    (net (code "124") (name "unconnected-(DJ1-PQ2-PadE3)") (class "Default")
      (node (ref "DJ1") (pin "E3") (pinfunction "PQ2_E3") (pintype "passive"))
    )
    (net (code "125") (name "unconnected-(DJ1-PQ3-PadF5)") (class "Default")
      (node (ref "DJ1") (pin "F5") (pinfunction "PQ3_F5") (pintype "passive"))
    )
    (net (code "126") (name "unconnected-(ID1-Pad6)") (class "Default")
      (node (ref "ID1") (pin "6") (pinfunction "6_6") (pintype "passive"))
    )
    (net (code "127") (name "unconnected-(PLD2-Pad8)") (class "Default")
      (node (ref "PLD2") (pin "8") (pinfunction "8_8") (pintype "passive"))
    )
    (net (code "128") (name "unconnected-(PLD2-Pad10)") (class "Default")
      (node (ref "PLD2") (pin "10") (pinfunction "10_10") (pintype "passive"))
    )
    (net (code "129") (name "unconnected-(PLDW1-Pad3)") (class "Default")
      (node (ref "PLDW1") (pin "3") (pinfunction "3_3") (pintype "passive"))
    )
    (net (code "130") (name "unconnected-(PLDW1-Pad4)") (class "Default")
      (node (ref "PLDW1") (pin "4") (pinfunction "4_4") (pintype "passive"))
    )
  )
)
